# rapidshark-main-breakout-top-mk-1_7.net
KiCad netlist of a schematic drawn in EAGLE
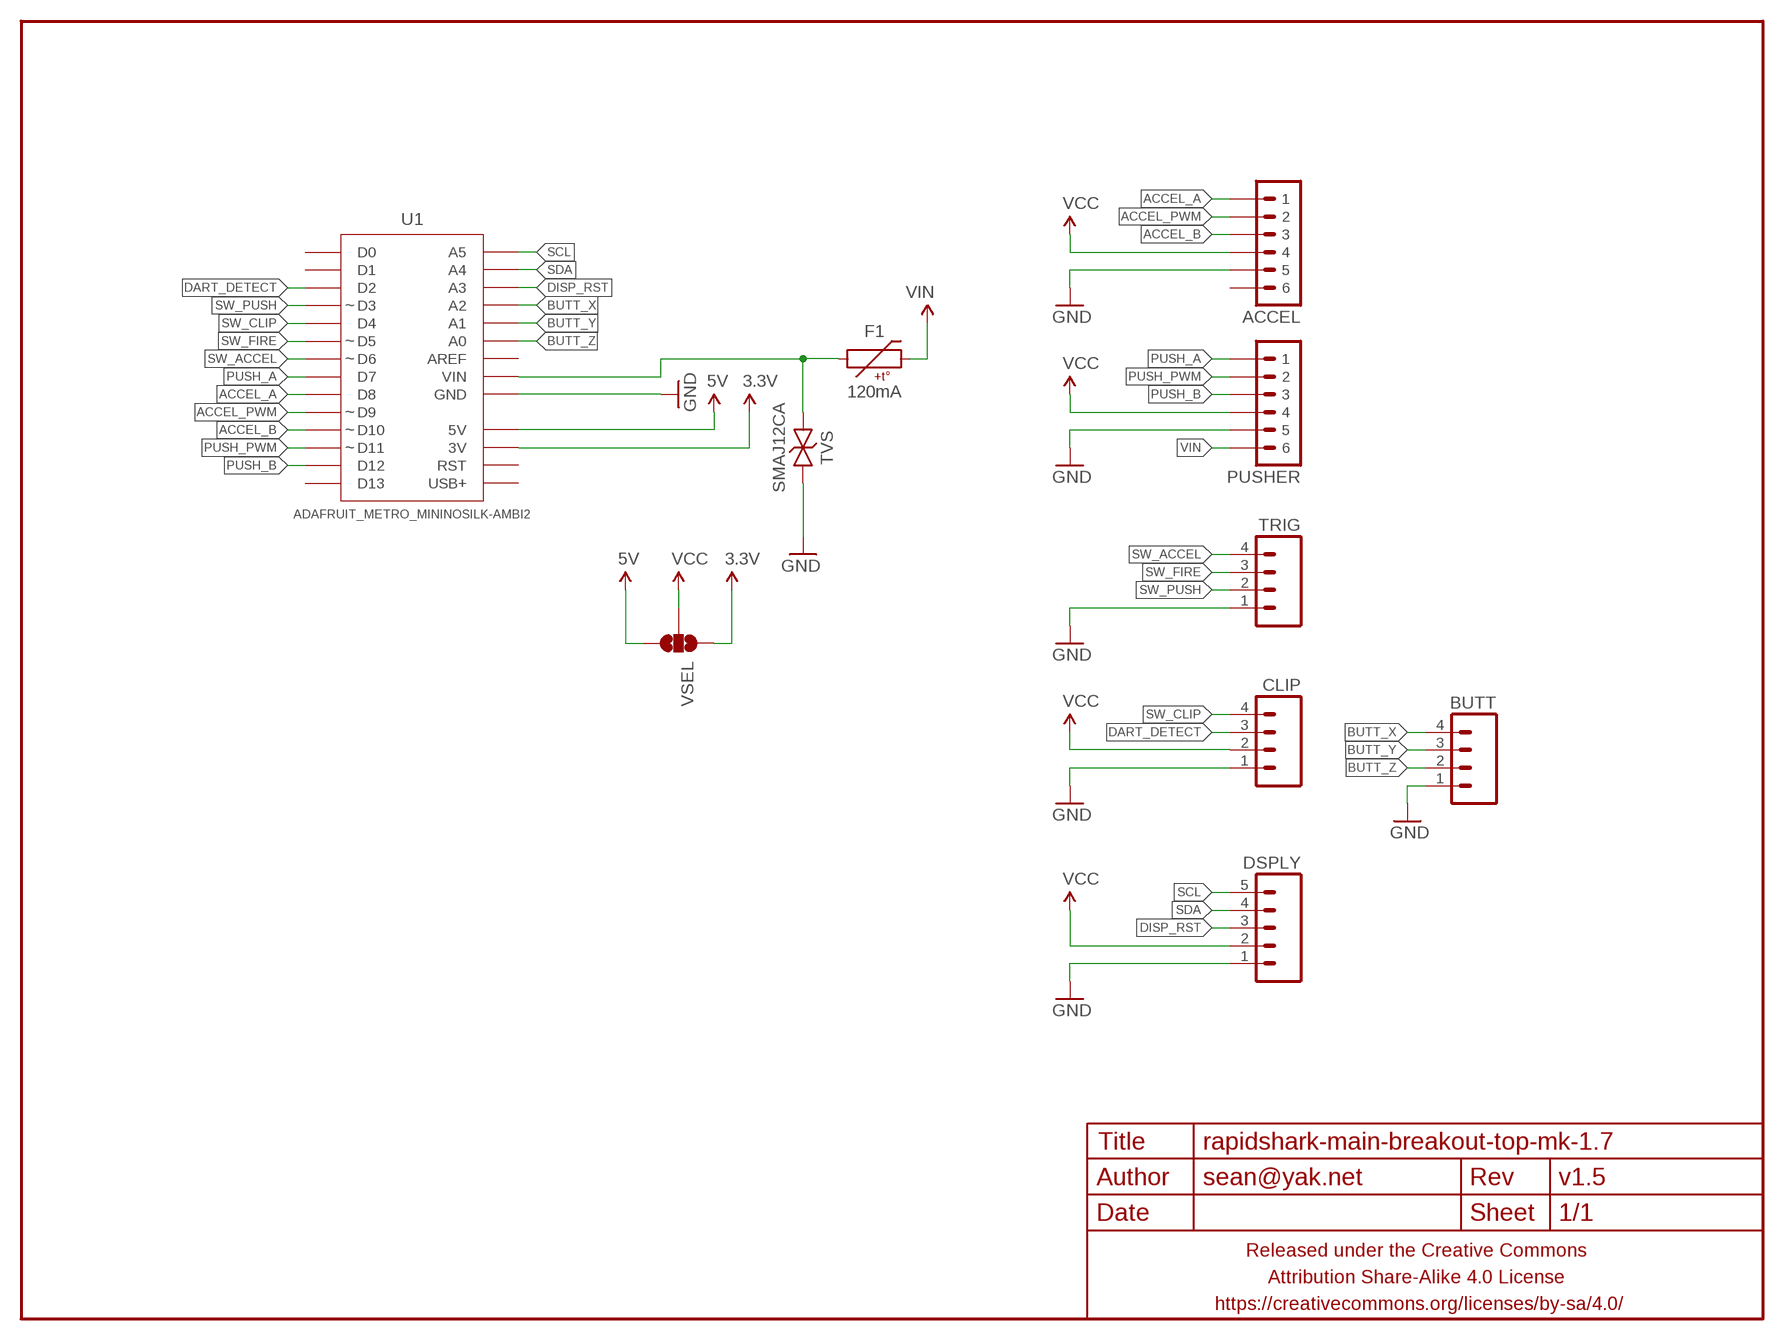
[diagram p0: schematic, sheet 1]

(export (version "E")
  (design (tool "Eeschema 10.0.6"))
  (components
    (comp (ref "ACCEL")
      (value "M06JST-PH-PTH-VERT")
      (footprint "eagle-import:JST-6-PH-VERT-PTH")
      (libsource (lib "eagle-import") (part "M06JST-PH-PTH-VERT"))
    )
    (comp (ref "BUTT")
      (value "M04JST-PTH-VERT")
      (footprint "eagle-import:JST-4-PH-VERT-PTH")
      (libsource (lib "eagle-import") (part "M04JST-PTH-VERT"))
    )
    (comp (ref "CLIP")
      (value "M04JST-PTH-VERT")
      (footprint "eagle-import:JST-4-PH-VERT-PTH")
      (libsource (lib "eagle-import") (part "M04JST-PTH-VERT"))
    )
    (comp (ref "DSPLY")
      (value "M05JST-PH-VERT-PTH")
      (footprint "eagle-import:JST-5-PH-VERT-PTH")
      (libsource (lib "eagle-import") (part "M05JST-PH-VERT-PTH"))
    )
    (comp (ref "F1")
      (value "120mA")
      (footprint "eagle-import:PTC-1206")
      (libsource (lib "eagle-import") (part "PTCSMD"))
    )
    (comp (ref "FRAME1")
      (value "FRAME-LETTERNO_PACKAGE")
      (footprint "eagle-import:DUMMY")
      (fields (field (name "DESIGNER") "sean@yak.net") (field (name "VERSION") "v1.5"))
      (libsource (lib "eagle-import") (part "FRAME-LETTERNO_PACKAGE"))
    )
    (comp (ref "PUSHER")
      (value "M06JST-PH-PTH-VERT")
      (footprint "eagle-import:JST-6-PH-VERT-PTH")
      (libsource (lib "eagle-import") (part "M06JST-PH-PTH-VERT"))
    )
    (comp (ref "TRIG")
      (value "M04JST-PTH-VERT")
      (footprint "eagle-import:JST-4-PH-VERT-PTH")
      (libsource (lib "eagle-import") (part "M04JST-PTH-VERT"))
    )
    (comp (ref "TVS")
      (value "SMAJ12CA")
      (footprint "eagle-import:SMA-DIODE-TVS-BIDIR")
      (libsource (lib "eagle-import") (part "TVSSMA"))
    )
    (comp (ref "U1")
      (value "ADAFRUIT_METRO_MININOSILK-AMBI2")
      (footprint "eagle-import:ADAFRUIT_METRO_MINI_BACK")
      (libsource (lib "eagle-import") (part "ADAFRUIT_METRO_MININOSILK-AMBI2"))
    )
    (comp (ref "VSEL")
      (value "JUMPER-PAD-3-NOFULL_BOX_SILK")
      (footprint "eagle-import:PAD-JUMPER-3-NO_YES_SILK_FULL_BOX")
      (libsource (lib "eagle-import") (part "JUMPER-PAD-3-NOFULL_BOX_SILK"))
    )
  )
  (nets
    (net (code "1") (name "3.3V") (class "Default")
      (node (ref "U1") (pin "17") (pinfunction "3V_17") (pintype "bidirectional"))
      (node (ref "VSEL") (pin "1") (pinfunction "1_1") (pintype "passive"))
    )
    (net (code "2") (name "5V") (class "Default")
      (node (ref "U1") (pin "18") (pinfunction "5V_18") (pintype "bidirectional"))
      (node (ref "VSEL") (pin "3") (pinfunction "3_3") (pintype "passive"))
    )
    (net (code "3") (name "ACCEL_A") (class "Default")
      (node (ref "ACCEL") (pin "1") (pinfunction "1_1") (pintype "passive"))
      (node (ref "U1") (pin "9") (pinfunction "D8_9") (pintype "bidirectional"))
    )
    (net (code "4") (name "ACCEL_B") (class "Default")
      (node (ref "ACCEL") (pin "3") (pinfunction "3_3") (pintype "passive"))
      (node (ref "U1") (pin "11") (pinfunction "D10_11") (pintype "bidirectional"))
    )
    (net (code "5") (name "ACCEL_PWM") (class "Default")
      (node (ref "ACCEL") (pin "2") (pinfunction "2_2") (pintype "passive"))
      (node (ref "U1") (pin "10") (pinfunction "D9_10") (pintype "bidirectional"))
    )
    (net (code "6") (name "BUTT_X") (class "Default")
      (node (ref "BUTT") (pin "4") (pinfunction "4_4") (pintype "passive"))
      (node (ref "U1") (pin "25") (pinfunction "A2_25") (pintype "bidirectional"))
    )
    (net (code "7") (name "BUTT_Y") (class "Default")
      (node (ref "BUTT") (pin "3") (pinfunction "3_3") (pintype "passive"))
      (node (ref "U1") (pin "24") (pinfunction "A1_24") (pintype "bidirectional"))
    )
    (net (code "8") (name "BUTT_Z") (class "Default")
      (node (ref "BUTT") (pin "2") (pinfunction "2_2") (pintype "passive"))
      (node (ref "U1") (pin "23") (pinfunction "A0_23") (pintype "bidirectional"))
    )
    (net (code "9") (name "DART_DETECT") (class "Default")
      (node (ref "CLIP") (pin "3") (pinfunction "3_3") (pintype "passive"))
      (node (ref "U1") (pin "3") (pinfunction "D2_3") (pintype "bidirectional"))
    )
    (net (code "10") (name "DISP_RST") (class "Default")
      (node (ref "DSPLY") (pin "3") (pinfunction "3_3") (pintype "passive"))
      (node (ref "U1") (pin "26") (pinfunction "A3_26") (pintype "bidirectional"))
    )
    (net (code "11") (name "GND") (class "Default")
      (node (ref "ACCEL") (pin "5") (pinfunction "5_5") (pintype "passive"))
      (node (ref "BUTT") (pin "1") (pinfunction "1_1") (pintype "passive"))
      (node (ref "CLIP") (pin "1") (pinfunction "1_1") (pintype "passive"))
      (node (ref "DSPLY") (pin "1") (pinfunction "1_1") (pintype "passive"))
      (node (ref "PUSHER") (pin "5") (pinfunction "5_5") (pintype "passive"))
      (node (ref "TRIG") (pin "1") (pinfunction "1_1") (pintype "passive"))
      (node (ref "TVS") (pin "1") (pinfunction "1_1") (pintype "passive"))
      (node (ref "U1") (pin "19") (pinfunction "GND_19") (pintype "bidirectional"))
      (node (ref "U1") (pin "20") (pinfunction "GND_20") (pintype "bidirectional"))
    )
    (net (code "12") (name "Net-(U1-VIN)") (class "Default")
      (node (ref "F1") (pin "1") (pinfunction "1_1") (pintype "passive"))
      (node (ref "TVS") (pin "2") (pinfunction "2_2") (pintype "passive"))
      (node (ref "U1") (pin "21") (pinfunction "VIN_21") (pintype "bidirectional"))
    )
    (net (code "13") (name "PUSH_A") (class "Default")
      (node (ref "PUSHER") (pin "1") (pinfunction "1_1") (pintype "passive"))
      (node (ref "U1") (pin "8") (pinfunction "D7_8") (pintype "bidirectional"))
    )
    (net (code "14") (name "PUSH_B") (class "Default")
      (node (ref "PUSHER") (pin "3") (pinfunction "3_3") (pintype "passive"))
      (node (ref "U1") (pin "13") (pinfunction "D12_13") (pintype "bidirectional"))
    )
    (net (code "15") (name "PUSH_PWM") (class "Default")
      (node (ref "PUSHER") (pin "2") (pinfunction "2_2") (pintype "passive"))
      (node (ref "U1") (pin "12") (pinfunction "D11_12") (pintype "bidirectional"))
    )
    (net (code "16") (name "SCL") (class "Default")
      (node (ref "DSPLY") (pin "5") (pinfunction "5_5") (pintype "passive"))
      (node (ref "U1") (pin "28") (pinfunction "A5_28") (pintype "bidirectional"))
    )
    (net (code "17") (name "SDA") (class "Default")
      (node (ref "DSPLY") (pin "4") (pinfunction "4_4") (pintype "passive"))
      (node (ref "U1") (pin "27") (pinfunction "A4_27") (pintype "bidirectional"))
    )
    (net (code "18") (name "SW_ACCEL") (class "Default")
      (node (ref "TRIG") (pin "4") (pinfunction "4_4") (pintype "passive"))
      (node (ref "U1") (pin "7") (pinfunction "D6_7") (pintype "bidirectional"))
    )
    (net (code "19") (name "SW_CLIP") (class "Default")
      (node (ref "CLIP") (pin "4") (pinfunction "4_4") (pintype "passive"))
      (node (ref "U1") (pin "5") (pinfunction "D4_5") (pintype "bidirectional"))
    )
    (net (code "20") (name "SW_FIRE") (class "Default")
      (node (ref "TRIG") (pin "3") (pinfunction "3_3") (pintype "passive"))
      (node (ref "U1") (pin "6") (pinfunction "D5_6") (pintype "bidirectional"))
    )
    (net (code "21") (name "SW_PUSH") (class "Default")
      (node (ref "TRIG") (pin "2") (pinfunction "2_2") (pintype "passive"))
      (node (ref "U1") (pin "4") (pinfunction "D3_4") (pintype "bidirectional"))
    )
    (net (code "22") (name "VCC") (class "Default")
      (node (ref "ACCEL") (pin "4") (pinfunction "4_4") (pintype "passive"))
      (node (ref "CLIP") (pin "2") (pinfunction "2_2") (pintype "passive"))
      (node (ref "DSPLY") (pin "2") (pinfunction "2_2") (pintype "passive"))
      (node (ref "PUSHER") (pin "4") (pinfunction "4_4") (pintype "passive"))
      (node (ref "VSEL") (pin "2") (pinfunction "2_2") (pintype "passive"))
    )
    (net (code "23") (name "VIN") (class "Default")
      (node (ref "F1") (pin "2") (pinfunction "2_2") (pintype "passive"))
      (node (ref "PUSHER") (pin "6") (pinfunction "6_6") (pintype "passive"))
    )
    (net (code "24") (name "unconnected-(ACCEL-Pad6)") (class "Default")
      (node (ref "ACCEL") (pin "6") (pinfunction "6_6") (pintype "passive"))
    )
    (net (code "25") (name "unconnected-(U1-AREF-Pad22)") (class "Default")
      (node (ref "U1") (pin "22") (pinfunction "AREF_22") (pintype "bidirectional"))
    )
    (net (code "26") (name "unconnected-(U1-D0-Pad1)") (class "Default")
      (node (ref "U1") (pin "1") (pinfunction "D0_1") (pintype "bidirectional"))
    )
    (net (code "27") (name "unconnected-(U1-D1-Pad2)") (class "Default")
      (node (ref "U1") (pin "2") (pinfunction "D1_2") (pintype "bidirectional"))
    )
    (net (code "28") (name "unconnected-(U1-D13-Pad14)") (class "Default")
      (node (ref "U1") (pin "14") (pinfunction "D13_14") (pintype "bidirectional"))
    )
    (net (code "29") (name "unconnected-(U1-RST-Pad16)") (class "Default")
      (node (ref "U1") (pin "16") (pinfunction "RST_16") (pintype "bidirectional"))
    )
    (net (code "30") (name "unconnected-(U1-USB+-Pad15)") (class "Default")
      (node (ref "U1") (pin "15") (pinfunction "USB+_15") (pintype "bidirectional"))
    )
  )
)
